# RS232.net
KiCad netlist of a schematic drawn in Altium Designer
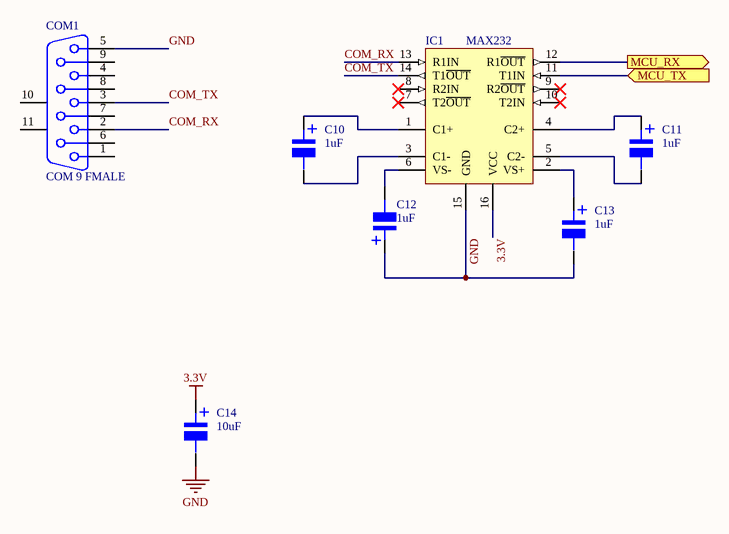
[diagram p0: RS232.SchDoc]

(export (version "E")
  (design (tool "Eeschema 10.0.6"))
  (components
    (comp (ref "C10")
      (value "1uF")
      (footprint "tu nhom 4 (B)")
      (description "Dán")
      (libsource (lib "Altium_Lib_by_KhueNguyenCreator") (part "Tu Nhom 1uF 50V"))
    )
    (comp (ref "C11")
      (value "1uF")
      (footprint "tu nhom 4 (B)")
      (description "Dán")
      (libsource (lib "Altium_Lib_by_KhueNguyenCreator") (part "Tu Nhom 1uF 50V"))
    )
    (comp (ref "C12")
      (value "1uF")
      (footprint "tu nhom 4 (B)")
      (description "Dán")
      (libsource (lib "") (part "Tu Nhom 1uF 50V_1"))
    )
    (comp (ref "C13")
      (value "1uF")
      (footprint "tu nhom 4 (B)")
      (description "Dán")
      (libsource (lib "Altium_Lib_by_KhueNguyenCreator") (part "Tu Nhom 1uF 50V"))
    )
    (comp (ref "C14")
      (value "10uF")
      (footprint "tu nhom 4 (b)")
      (description "Dán")
      (libsource (lib "Altium_Lib_by_KhueNguyenCreator") (part "Tu Nhom 10uF 16V"))
    )
    (comp (ref "COM1")
      (value "COM 9 FMALE")
      (footprint "DSB 9-F")
      (description "COM 9")
      (fields (field (name "PUBLISHER") "Altium Limited"))
      (libsource (lib "syhaunguyen") (part "DSB9F"))
    )
    (comp (ref "IC1")
      (value "MAX232")
      (footprint "DIP16/W0.3")
      (description "Dual EIA-232 Driver/Receiver")
      (libsource (lib "syhaunguyen") (part "MAX232"))
    )
  )
  (nets
    (net (code "1") (name "/COM_RX") (class "Default")
      (node (ref "COM1") (pin "2") (pinfunction "2_2") (pintype "passive"))
      (node (ref "IC1") (pin "13") (pinfunction "R1IN_13") (pintype "input"))
    )
    (net (code "2") (name "/COM_TX") (class "Default")
      (node (ref "COM1") (pin "3") (pinfunction "3_3") (pintype "passive"))
      (node (ref "IC1") (pin "14") (pinfunction "T1~{OUT}_14") (pintype "output"))
    )
    (net (code "3") (name "/MCU_RX") (class "Default")
      (node (ref "IC1") (pin "12") (pinfunction "R1~{OUT}_12") (pintype "output"))
    )
    (net (code "4") (name "/MCU_TX") (class "Default")
      (node (ref "IC1") (pin "11") (pinfunction "T1IN_11") (pintype "input"))
    )
    (net (code "5") (name "3.3V") (class "Default")
      (node (ref "C14") (pin "1") (pinfunction "1_1") (pintype "passive"))
      (node (ref "IC1") (pin "16") (pinfunction "VCC_16") (pintype "power_in"))
    )
    (net (code "6") (name "GND") (class "Default")
      (node (ref "C12") (pin "1") (pinfunction "1_1") (pintype "passive"))
      (node (ref "C13") (pin "2") (pinfunction "2_2") (pintype "passive"))
      (node (ref "C14") (pin "2") (pinfunction "2_2") (pintype "passive"))
      (node (ref "COM1") (pin "5") (pinfunction "5_5") (pintype "passive"))
      (node (ref "IC1") (pin "15") (pinfunction "GND_15") (pintype "power_in"))
    )
    (net (code "7") (name "Net-(IC1-C1+)") (class "Default")
      (node (ref "C10") (pin "1") (pinfunction "1_1") (pintype "passive"))
      (node (ref "IC1") (pin "1") (pinfunction "C1+_1") (pintype "passive"))
    )
    (net (code "8") (name "Net-(IC1-C1-)") (class "Default")
      (node (ref "C10") (pin "2") (pinfunction "2_2") (pintype "passive"))
      (node (ref "IC1") (pin "3") (pinfunction "C1-_3") (pintype "passive"))
    )
    (net (code "9") (name "Net-(IC1-C2+)") (class "Default")
      (node (ref "C11") (pin "1") (pinfunction "1_1") (pintype "passive"))
      (node (ref "IC1") (pin "4") (pinfunction "C2+_4") (pintype "passive"))
    )
    (net (code "10") (name "Net-(IC1-C2-)") (class "Default")
      (node (ref "C11") (pin "2") (pinfunction "2_2") (pintype "passive"))
      (node (ref "IC1") (pin "5") (pinfunction "C2-_5") (pintype "passive"))
    )
    (net (code "11") (name "Net-(IC1-VS+)") (class "Default")
      (node (ref "C13") (pin "1") (pinfunction "1_1") (pintype "passive"))
      (node (ref "IC1") (pin "2") (pinfunction "VS+_2") (pintype "power_in"))
    )
    (net (code "12") (name "Net-(IC1-VS-)") (class "Default")
      (node (ref "C12") (pin "2") (pinfunction "2_2") (pintype "passive"))
      (node (ref "IC1") (pin "6") (pinfunction "VS-_6") (pintype "power_in"))
    )
    (net (code "13") (name "unconnected-(COM1-MH1-Pad10)") (class "Default")
      (node (ref "COM1") (pin "10") (pinfunction "MH1_10") (pintype "passive"))
    )
    (net (code "14") (name "unconnected-(COM1-MH2-Pad11)") (class "Default")
      (node (ref "COM1") (pin "11") (pinfunction "MH2_11") (pintype "passive"))
    )
    (net (code "15") (name "unconnected-(COM1-Pad1)") (class "Default")
      (node (ref "COM1") (pin "1") (pinfunction "1_1") (pintype "passive"))
    )
    (net (code "16") (name "unconnected-(COM1-Pad4)") (class "Default")
      (node (ref "COM1") (pin "4") (pinfunction "4_4") (pintype "passive"))
    )
    (net (code "17") (name "unconnected-(COM1-Pad6)") (class "Default")
      (node (ref "COM1") (pin "6") (pinfunction "6_6") (pintype "passive"))
    )
    (net (code "18") (name "unconnected-(COM1-Pad7)") (class "Default")
      (node (ref "COM1") (pin "7") (pinfunction "7_7") (pintype "passive"))
    )
    (net (code "19") (name "unconnected-(COM1-Pad8)") (class "Default")
      (node (ref "COM1") (pin "8") (pinfunction "8_8") (pintype "passive"))
    )
    (net (code "20") (name "unconnected-(COM1-Pad9)") (class "Default")
      (node (ref "COM1") (pin "9") (pinfunction "9_9") (pintype "passive"))
    )
    (net (code "21") (name "unconnected-(IC1-R2IN-Pad8)") (class "Default")
      (node (ref "IC1") (pin "8") (pinfunction "R2IN_8") (pintype "input+no_connect"))
    )
    (net (code "22") (name "unconnected-(IC1-R2~{OUT}-Pad9)") (class "Default")
      (node (ref "IC1") (pin "9") (pinfunction "R2~{OUT}_9") (pintype "output+no_connect"))
    )
    (net (code "23") (name "unconnected-(IC1-T2IN-Pad10)") (class "Default")
      (node (ref "IC1") (pin "10") (pinfunction "T2IN_10") (pintype "input+no_connect"))
    )
    (net (code "24") (name "unconnected-(IC1-T2~{OUT}-Pad7)") (class "Default")
      (node (ref "IC1") (pin "7") (pinfunction "T2~{OUT}_7") (pintype "output+no_connect"))
    )
  )
)
